# analog-interface.net
KiCad netlist of a schematic drawn in EAGLE
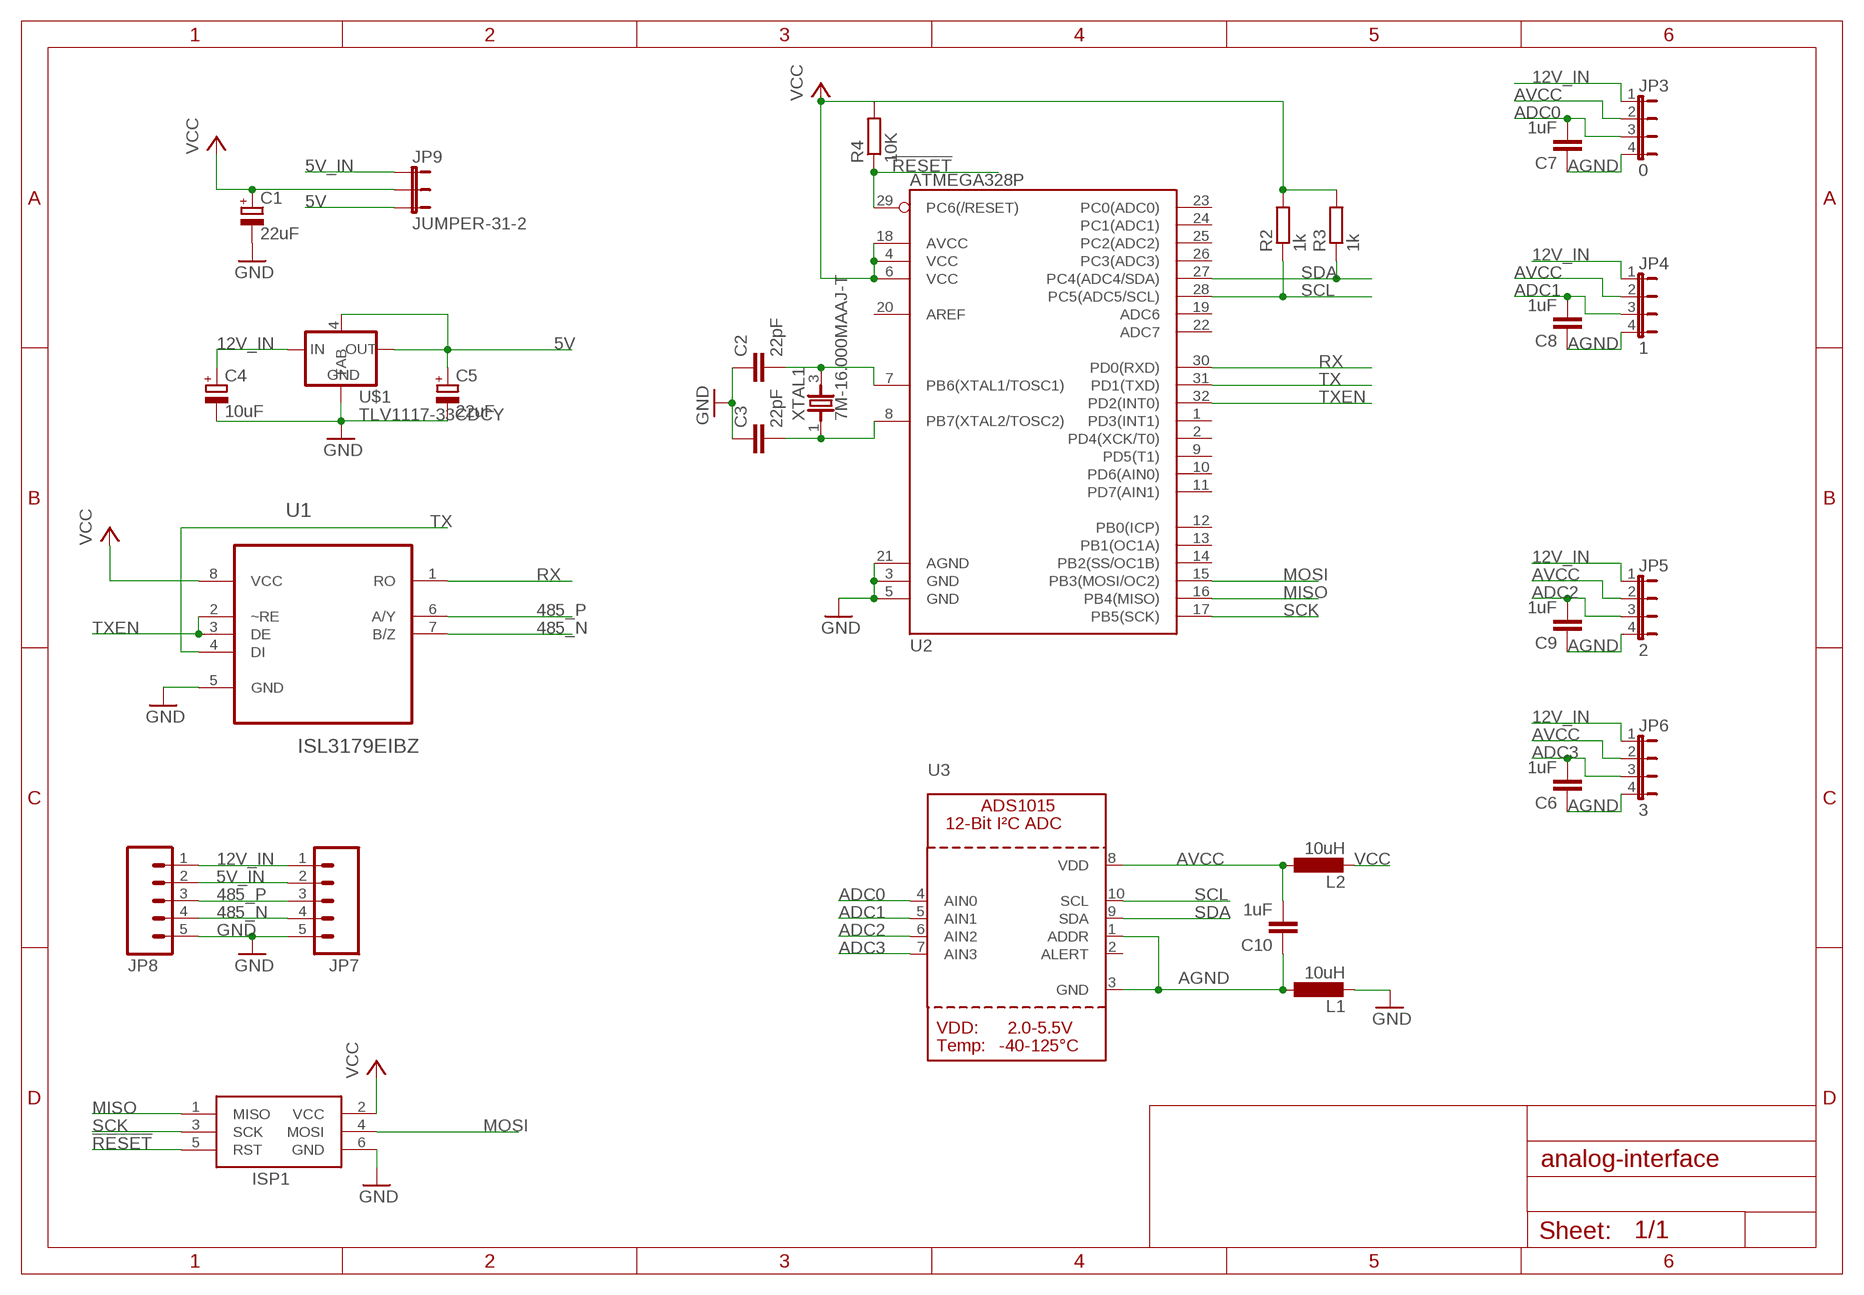
[diagram p0: schematic, sheet 1]

(export (version "E")
  (design (tool "Eeschema 10.0.6"))
  (components
    (comp (ref "C1")
      (value "22uF")
      (footprint "eagle-import:A_3216-18R")
      (libsource (lib "eagle-import") (part "CPOL-EUA/3216-18R"))
    )
    (comp (ref "C2")
      (value "22pF")
      (footprint "eagle-import:C0805")
      (libsource (lib "eagle-import") (part "C-EUC0805"))
    )
    (comp (ref "C3")
      (value "22pF")
      (footprint "eagle-import:C0805")
      (libsource (lib "eagle-import") (part "C-EUC0805"))
    )
    (comp (ref "C4")
      (value "10uF")
      (footprint "eagle-import:A_3216-18R")
      (libsource (lib "eagle-import") (part "CPOL-EUA/3216-18R"))
    )
    (comp (ref "C5")
      (value "22uF")
      (footprint "eagle-import:A_3216-18R")
      (libsource (lib "eagle-import") (part "CPOL-EUA/3216-18R"))
    )
    (comp (ref "C6")
      (value "1uF")
      (footprint "eagle-import:C0805")
      (libsource (lib "eagle-import") (part "C-EUC0805"))
    )
    (comp (ref "C7")
      (value "1uF")
      (footprint "eagle-import:C0805")
      (libsource (lib "eagle-import") (part "C-EUC0805"))
    )
    (comp (ref "C8")
      (value "1uF")
      (footprint "eagle-import:C0805")
      (libsource (lib "eagle-import") (part "C-EUC0805"))
    )
    (comp (ref "C9")
      (value "1uF")
      (footprint "eagle-import:C0805")
      (libsource (lib "eagle-import") (part "C-EUC0805"))
    )
    (comp (ref "C10")
      (value "1uF")
      (footprint "eagle-import:C0805")
      (libsource (lib "eagle-import") (part "C-EUC0805"))
    )
    (comp (ref "ISP1")
      (value "AVRISP-6")
      (footprint "eagle-import:AVRISP")
      (libsource (lib "eagle-import") (part "AVRISP-6"))
    )
    (comp (ref "JP3")
      (value "0")
      (footprint "eagle-import:JP4")
      (libsource (lib "eagle-import") (part "JP4E"))
    )
    (comp (ref "JP4")
      (value "1")
      (footprint "eagle-import:JP4")
      (libsource (lib "eagle-import") (part "JP4E"))
    )
    (comp (ref "JP5")
      (value "2")
      (footprint "eagle-import:JP4")
      (libsource (lib "eagle-import") (part "JP4E"))
    )
    (comp (ref "JP6")
      (value "3")
      (footprint "eagle-import:JP4")
      (libsource (lib "eagle-import") (part "JP4E"))
    )
    (comp (ref "JP7")
      (value "M05PTH")
      (footprint "eagle-import:1X05")
      (libsource (lib "eagle-import") (part "M05PTH"))
    )
    (comp (ref "JP8")
      (value "M05PTH")
      (footprint "eagle-import:1X05")
      (libsource (lib "eagle-import") (part "M05PTH"))
    )
    (comp (ref "JP9")
      (value "JUMPER-31-2")
      (footprint "eagle-import:SJ_3_PASTE1&2")
      (libsource (lib "eagle-import") (part "JUMPER-31-2"))
    )
    (comp (ref "L1")
      (value "10uH")
      (footprint "eagle-import:L3216C")
      (libsource (lib "eagle-import") (part "L-EUL3216C"))
    )
    (comp (ref "L2")
      (value "10uH")
      (footprint "eagle-import:L3216C")
      (libsource (lib "eagle-import") (part "L-EUL3216C"))
    )
    (comp (ref "R2")
      (value "1k")
      (footprint "eagle-import:R0805")
      (libsource (lib "eagle-import") (part "R-EU_R0805"))
    )
    (comp (ref "R3")
      (value "1k")
      (footprint "eagle-import:R0805")
      (libsource (lib "eagle-import") (part "R-EU_R0805"))
    )
    (comp (ref "R4")
      (value "10K")
      (footprint "eagle-import:R0805")
      (libsource (lib "eagle-import") (part "R-EU_R0805"))
    )
    (comp (ref "U$1")
      (value "TLV1117-33CDCY")
      (footprint "eagle-import:SOT223")
      (libsource (lib "eagle-import") (part "TLV1117-33CDCY"))
    )
    (comp (ref "U1")
      (value "ISL3179EIBZ")
      (footprint "eagle-import:SOIC127P600X175-8N")
      (libsource (lib "eagle-import") (part "ISL3179EIBZ"))
    )
    (comp (ref "U2")
      (value "ATMEGA328P")
      (footprint "eagle-import:TQFP32-08")
      (libsource (lib "eagle-import") (part "ATMEGA328_SMT"))
    )
    (comp (ref "U3")
      (value "ADC_ADS1015")
      (footprint "eagle-import:MSOP10")
      (libsource (lib "eagle-import") (part "ADC_ADS1015"))
    )
    (comp (ref "XTAL1")
      (value "7M-16.000MAAJ-T")
      (footprint "eagle-import:TXC_7M-16.000MAAJ-T")
      (fields (field (name "MPN") "7M-16.000MAAJ-T "))
      (libsource (lib "eagle-import") (part "7M-16.000MAAJ-T"))
    )
  )
  (nets
    (net (code "1") (name "/5V") (class "Default")
      (node (ref "C5") (pin "+") (pinfunction "+_+") (pintype "passive"))
      (node (ref "JP9") (pin "3") (pinfunction "3_3") (pintype "passive"))
      (node (ref "U$1") (pin "2") (pinfunction "OUT_2") (pintype "passive"))
      (node (ref "U$1") (pin "4") (pinfunction "TAB_4") (pintype "passive"))
    )
    (net (code "2") (name "/5V_IN") (class "Default")
      (node (ref "JP7") (pin "2") (pinfunction "2_2") (pintype "passive"))
      (node (ref "JP8") (pin "2") (pinfunction "2_2") (pintype "passive"))
      (node (ref "JP9") (pin "1") (pinfunction "1_1") (pintype "passive"))
    )
    (net (code "3") (name "/12V_IN") (class "Default")
      (node (ref "C4") (pin "+") (pinfunction "+_+") (pintype "passive"))
      (node (ref "JP3") (pin "1") (pinfunction "1_1") (pintype "passive"))
      (node (ref "JP4") (pin "1") (pinfunction "1_1") (pintype "passive"))
      (node (ref "JP5") (pin "1") (pinfunction "1_1") (pintype "passive"))
      (node (ref "JP6") (pin "1") (pinfunction "1_1") (pintype "passive"))
      (node (ref "JP7") (pin "1") (pinfunction "1_1") (pintype "passive"))
      (node (ref "JP8") (pin "1") (pinfunction "1_1") (pintype "passive"))
      (node (ref "U$1") (pin "3") (pinfunction "IN_3") (pintype "input"))
    )
    (net (code "4") (name "/485_N") (class "Default")
      (node (ref "JP7") (pin "4") (pinfunction "4_4") (pintype "passive"))
      (node (ref "JP8") (pin "4") (pinfunction "4_4") (pintype "passive"))
      (node (ref "U1") (pin "7") (pinfunction "B/Z_7") (pintype "bidirectional"))
    )
    (net (code "5") (name "/485_P") (class "Default")
      (node (ref "JP7") (pin "3") (pinfunction "3_3") (pintype "passive"))
      (node (ref "JP8") (pin "3") (pinfunction "3_3") (pintype "passive"))
      (node (ref "U1") (pin "6") (pinfunction "A/Y_6") (pintype "bidirectional"))
    )
    (net (code "6") (name "/ADC0") (class "Default")
      (node (ref "C7") (pin "2") (pinfunction "2_2") (pintype "passive"))
      (node (ref "JP3") (pin "3") (pinfunction "3_3") (pintype "passive"))
      (node (ref "U3") (pin "4") (pinfunction "AIN0_4") (pintype "bidirectional"))
    )
    (net (code "7") (name "/ADC1") (class "Default")
      (node (ref "C8") (pin "2") (pinfunction "2_2") (pintype "passive"))
      (node (ref "JP4") (pin "3") (pinfunction "3_3") (pintype "passive"))
      (node (ref "U3") (pin "5") (pinfunction "AIN1_5") (pintype "bidirectional"))
    )
    (net (code "8") (name "/ADC2") (class "Default")
      (node (ref "C9") (pin "2") (pinfunction "2_2") (pintype "passive"))
      (node (ref "JP5") (pin "3") (pinfunction "3_3") (pintype "passive"))
      (node (ref "U3") (pin "6") (pinfunction "AIN2_6") (pintype "bidirectional"))
    )
    (net (code "9") (name "/ADC3") (class "Default")
      (node (ref "C6") (pin "2") (pinfunction "2_2") (pintype "passive"))
      (node (ref "JP6") (pin "3") (pinfunction "3_3") (pintype "passive"))
      (node (ref "U3") (pin "7") (pinfunction "AIN3_7") (pintype "bidirectional"))
    )
    (net (code "10") (name "/AGND") (class "Default")
      (node (ref "C10") (pin "1") (pinfunction "1_1") (pintype "passive"))
      (node (ref "C6") (pin "1") (pinfunction "1_1") (pintype "passive"))
      (node (ref "C7") (pin "1") (pinfunction "1_1") (pintype "passive"))
      (node (ref "C8") (pin "1") (pinfunction "1_1") (pintype "passive"))
      (node (ref "C9") (pin "1") (pinfunction "1_1") (pintype "passive"))
      (node (ref "JP3") (pin "4") (pinfunction "4_4") (pintype "passive"))
      (node (ref "JP4") (pin "4") (pinfunction "4_4") (pintype "passive"))
      (node (ref "JP5") (pin "4") (pinfunction "4_4") (pintype "passive"))
      (node (ref "JP6") (pin "4") (pinfunction "4_4") (pintype "passive"))
      (node (ref "L1") (pin "1") (pinfunction "1_1") (pintype "passive"))
      (node (ref "U3") (pin "1") (pinfunction "ADDR_1") (pintype "bidirectional"))
      (node (ref "U3") (pin "3") (pinfunction "GND_3") (pintype "bidirectional"))
    )
    (net (code "11") (name "/AVCC") (class "Default")
      (node (ref "C10") (pin "2") (pinfunction "2_2") (pintype "passive"))
      (node (ref "JP3") (pin "2") (pinfunction "2_2") (pintype "passive"))
      (node (ref "JP4") (pin "2") (pinfunction "2_2") (pintype "passive"))
      (node (ref "JP5") (pin "2") (pinfunction "2_2") (pintype "passive"))
      (node (ref "JP6") (pin "2") (pinfunction "2_2") (pintype "passive"))
      (node (ref "L2") (pin "1") (pinfunction "1_1") (pintype "passive"))
      (node (ref "U3") (pin "8") (pinfunction "VDD_8") (pintype "bidirectional"))
    )
    (net (code "12") (name "/MISO") (class "Default")
      (node (ref "ISP1") (pin "1") (pinfunction "MISO_1") (pintype "input"))
      (node (ref "U2") (pin "16") (pinfunction "PB4(MISO)_16") (pintype "bidirectional"))
    )
    (net (code "13") (name "/MOSI") (class "Default")
      (node (ref "ISP1") (pin "4") (pinfunction "MOSI_4") (pintype "output"))
      (node (ref "U2") (pin "15") (pinfunction "PB3(MOSI/OC2)_15") (pintype "bidirectional"))
    )
    (net (code "14") (name "/RX") (class "Default")
      (node (ref "U1") (pin "1") (pinfunction "RO_1") (pintype "output"))
      (node (ref "U2") (pin "30") (pinfunction "PD0(RXD)_30") (pintype "bidirectional"))
    )
    (net (code "15") (name "/SCK") (class "Default")
      (node (ref "ISP1") (pin "3") (pinfunction "SCK_3") (pintype "output"))
      (node (ref "U2") (pin "17") (pinfunction "PB5(SCK)_17") (pintype "bidirectional"))
    )
    (net (code "16") (name "/SCL") (class "Default")
      (node (ref "R2") (pin "1") (pinfunction "1_1") (pintype "passive"))
      (node (ref "U2") (pin "28") (pinfunction "PC5(ADC5/SCL)_28") (pintype "bidirectional"))
      (node (ref "U3") (pin "10") (pinfunction "SCL_10") (pintype "bidirectional"))
    )
    (net (code "17") (name "/SDA") (class "Default")
      (node (ref "R3") (pin "1") (pinfunction "1_1") (pintype "passive"))
      (node (ref "U2") (pin "27") (pinfunction "PC4(ADC4/SDA)_27") (pintype "bidirectional"))
      (node (ref "U3") (pin "9") (pinfunction "SDA_9") (pintype "bidirectional"))
    )
    (net (code "18") (name "/TX") (class "Default")
      (node (ref "U1") (pin "4") (pinfunction "DI_4") (pintype "input"))
      (node (ref "U2") (pin "31") (pinfunction "PD1(TXD)_31") (pintype "bidirectional"))
    )
    (net (code "19") (name "/TXEN") (class "Default")
      (node (ref "U1") (pin "2") (pinfunction "~{RE}_2") (pintype "input"))
      (node (ref "U1") (pin "3") (pinfunction "DE_3") (pintype "input"))
      (node (ref "U2") (pin "32") (pinfunction "PD2(INT0)_32") (pintype "bidirectional"))
    )
    (net (code "20") (name "/~{RESET}") (class "Default")
      (node (ref "ISP1") (pin "5") (pinfunction "RST_5") (pintype "output"))
      (node (ref "R4") (pin "1") (pinfunction "1_1") (pintype "passive"))
      (node (ref "U2") (pin "29") (pinfunction "PC6(/RESET)_29") (pintype "bidirectional"))
    )
    (net (code "21") (name "GND") (class "Default")
      (node (ref "C1") (pin "-") (pinfunction "-_-") (pintype "passive"))
      (node (ref "C2") (pin "1") (pinfunction "1_1") (pintype "passive"))
      (node (ref "C3") (pin "1") (pinfunction "1_1") (pintype "passive"))
      (node (ref "C4") (pin "-") (pinfunction "-_-") (pintype "passive"))
      (node (ref "C5") (pin "-") (pinfunction "-_-") (pintype "passive"))
      (node (ref "ISP1") (pin "6") (pinfunction "GND_6") (pintype "power_in"))
      (node (ref "JP7") (pin "5") (pinfunction "5_5") (pintype "passive"))
      (node (ref "JP8") (pin "5") (pinfunction "5_5") (pintype "passive"))
      (node (ref "L1") (pin "2") (pinfunction "2_2") (pintype "passive"))
      (node (ref "U$1") (pin "1") (pinfunction "GND_1") (pintype "input"))
      (node (ref "U1") (pin "5") (pinfunction "GND_5") (pintype "passive"))
      (node (ref "U2") (pin "21") (pinfunction "AGND_21") (pintype "bidirectional"))
      (node (ref "U2") (pin "3") (pinfunction "GND_3") (pintype "bidirectional"))
      (node (ref "U2") (pin "5") (pinfunction "GND_5") (pintype "bidirectional"))
    )
    (net (code "22") (name "Net-(U2-PB6(XTAL1{slash}TOSC1))") (class "Default")
      (node (ref "C2") (pin "2") (pinfunction "2_2") (pintype "passive"))
      (node (ref "U2") (pin "7") (pinfunction "PB6(XTAL1/TOSC1)_7") (pintype "bidirectional"))
      (node (ref "XTAL1") (pin "3") (pinfunction "3_3") (pintype "passive"))
    )
    (net (code "23") (name "Net-(U2-PB7(XTAL2{slash}TOSC2))") (class "Default")
      (node (ref "C3") (pin "2") (pinfunction "2_2") (pintype "passive"))
      (node (ref "U2") (pin "8") (pinfunction "PB7(XTAL2/TOSC2)_8") (pintype "bidirectional"))
      (node (ref "XTAL1") (pin "1") (pinfunction "1_1") (pintype "passive"))
    )
    (net (code "24") (name "VCC") (class "Default")
      (node (ref "C1") (pin "+") (pinfunction "+_+") (pintype "passive"))
      (node (ref "ISP1") (pin "2") (pinfunction "VCC_2") (pintype "power_in"))
      (node (ref "JP9") (pin "2") (pinfunction "2_2") (pintype "passive"))
      (node (ref "L2") (pin "2") (pinfunction "2_2") (pintype "passive"))
      (node (ref "R2") (pin "2") (pinfunction "2_2") (pintype "passive"))
      (node (ref "R3") (pin "2") (pinfunction "2_2") (pintype "passive"))
      (node (ref "R4") (pin "2") (pinfunction "2_2") (pintype "passive"))
      (node (ref "U1") (pin "8") (pinfunction "VCC_8") (pintype "power_in"))
      (node (ref "U2") (pin "18") (pinfunction "AVCC_18") (pintype "bidirectional"))
      (node (ref "U2") (pin "4") (pinfunction "VCC_4") (pintype "bidirectional"))
      (node (ref "U2") (pin "6") (pinfunction "VCC_6") (pintype "bidirectional"))
    )
    (net (code "25") (name "unconnected-(U2-ADC6-Pad19)") (class "Default")
      (node (ref "U2") (pin "19") (pinfunction "ADC6_19") (pintype "bidirectional"))
    )
    (net (code "26") (name "unconnected-(U2-ADC7-Pad22)") (class "Default")
      (node (ref "U2") (pin "22") (pinfunction "ADC7_22") (pintype "bidirectional"))
    )
    (net (code "27") (name "unconnected-(U2-AREF-Pad20)") (class "Default")
      (node (ref "U2") (pin "20") (pinfunction "AREF_20") (pintype "bidirectional"))
    )
    (net (code "28") (name "unconnected-(U2-PB0(ICP)-Pad12)") (class "Default")
      (node (ref "U2") (pin "12") (pinfunction "PB0(ICP)_12") (pintype "bidirectional"))
    )
    (net (code "29") (name "unconnected-(U2-PB1(OC1A)-Pad13)") (class "Default")
      (node (ref "U2") (pin "13") (pinfunction "PB1(OC1A)_13") (pintype "bidirectional"))
    )
    (net (code "30") (name "unconnected-(U2-PB2(SS{slash}OC1B)-Pad14)") (class "Default")
      (node (ref "U2") (pin "14") (pinfunction "PB2(SS/OC1B)_14") (pintype "bidirectional"))
    )
    (net (code "31") (name "unconnected-(U2-PC0(ADC0)-Pad23)") (class "Default")
      (node (ref "U2") (pin "23") (pinfunction "PC0(ADC0)_23") (pintype "bidirectional"))
    )
    (net (code "32") (name "unconnected-(U2-PC1(ADC1)-Pad24)") (class "Default")
      (node (ref "U2") (pin "24") (pinfunction "PC1(ADC1)_24") (pintype "bidirectional"))
    )
    (net (code "33") (name "unconnected-(U2-PC2(ADC2)-Pad25)") (class "Default")
      (node (ref "U2") (pin "25") (pinfunction "PC2(ADC2)_25") (pintype "bidirectional"))
    )
    (net (code "34") (name "unconnected-(U2-PC3(ADC3)-Pad26)") (class "Default")
      (node (ref "U2") (pin "26") (pinfunction "PC3(ADC3)_26") (pintype "bidirectional"))
    )
    (net (code "35") (name "unconnected-(U2-PD3(INT1)-Pad1)") (class "Default")
      (node (ref "U2") (pin "1") (pinfunction "PD3(INT1)_1") (pintype "bidirectional"))
    )
    (net (code "36") (name "unconnected-(U2-PD4(XCK{slash}T0)-Pad2)") (class "Default")
      (node (ref "U2") (pin "2") (pinfunction "PD4(XCK/T0)_2") (pintype "bidirectional"))
    )
    (net (code "37") (name "unconnected-(U2-PD5(T1)-Pad9)") (class "Default")
      (node (ref "U2") (pin "9") (pinfunction "PD5(T1)_9") (pintype "bidirectional"))
    )
    (net (code "38") (name "unconnected-(U2-PD6(AIN0)-Pad10)") (class "Default")
      (node (ref "U2") (pin "10") (pinfunction "PD6(AIN0)_10") (pintype "bidirectional"))
    )
    (net (code "39") (name "unconnected-(U2-PD7(AIN1)-Pad11)") (class "Default")
      (node (ref "U2") (pin "11") (pinfunction "PD7(AIN1)_11") (pintype "bidirectional"))
    )
    (net (code "40") (name "unconnected-(U3-ALERT-Pad2)") (class "Default")
      (node (ref "U3") (pin "2") (pinfunction "ALERT_2") (pintype "bidirectional"))
    )
  )
)
